# Sheet1.net
KiCad netlist of a schematic drawn in Altium Designer
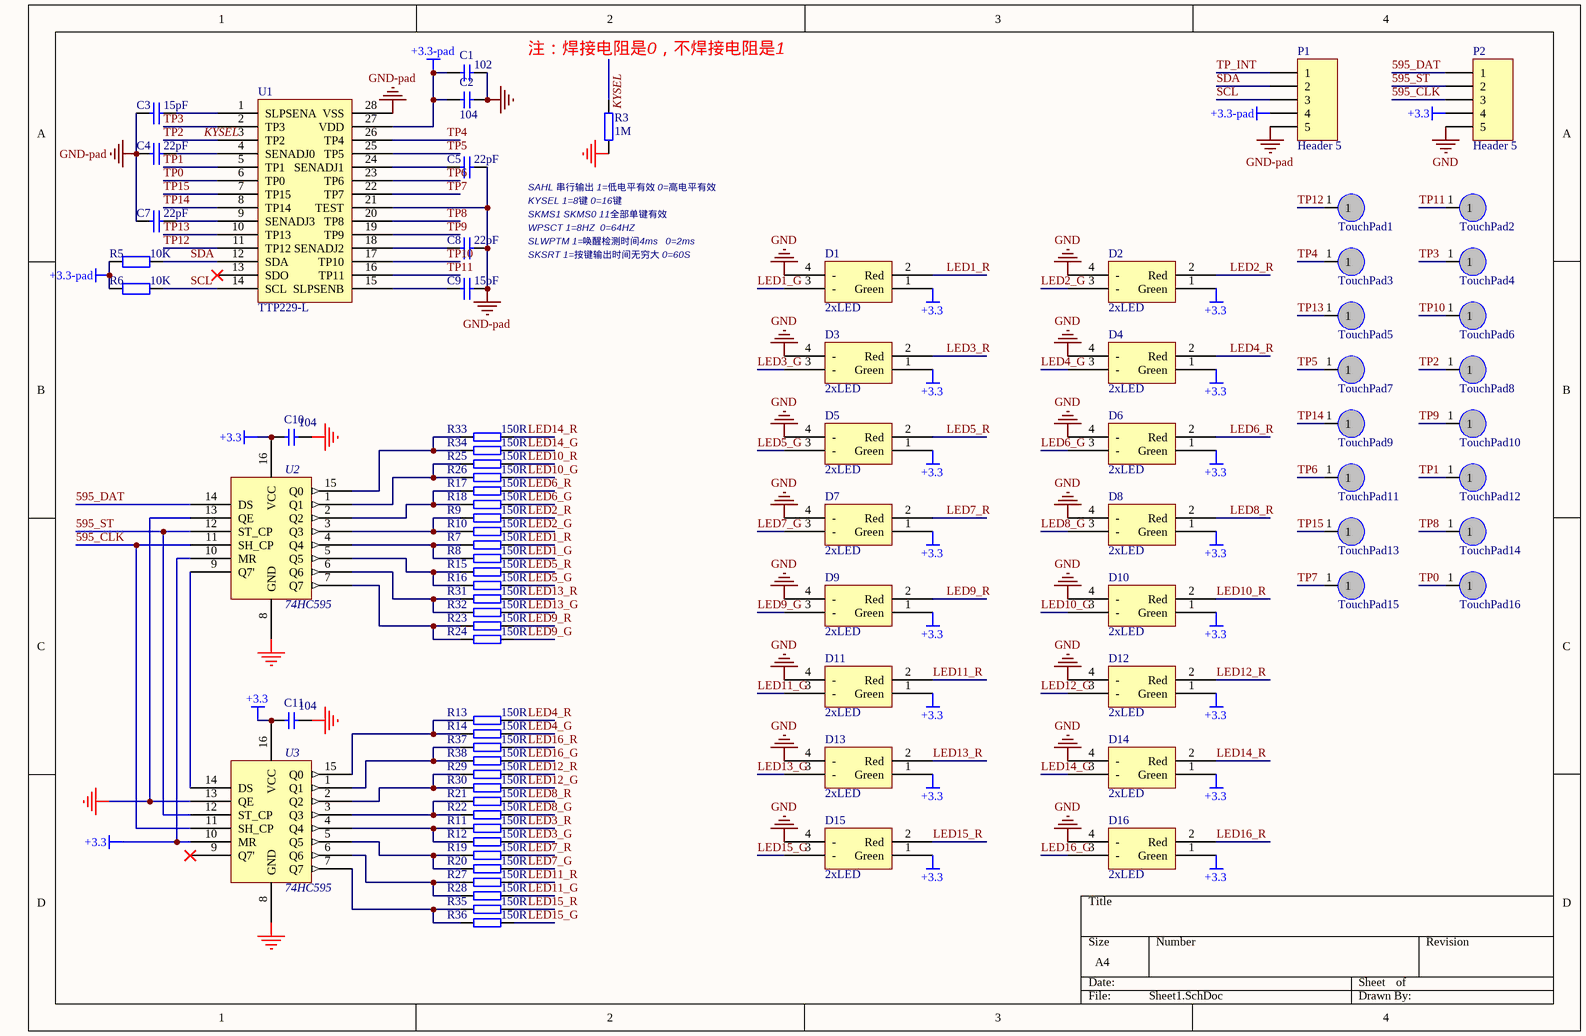
[diagram p0: Sheet1.SchDoc]

(export (version "E")
  (design (tool "Eeschema 10.0.6"))
  (components
    (comp (ref "C1")
      (value "102")
      (footprint "0603p")
      (description "0603/NPO")
      (libsource (lib "*") (part "电容-NPO-0603"))
    )
    (comp (ref "C2")
      (value "104")
      (footprint "0603p")
      (description "0603/NPO")
      (libsource (lib "*") (part "电容-NPO-0603"))
    )
    (comp (ref "C3")
      (value "15pF")
      (footprint "0603p")
      (description "Capacitor")
      (fields (field (name "PUBLISHER") "Altium Limited"))
      (libsource (lib "Miscellaneous Devices") (part "Cap"))
    )
    (comp (ref "C4")
      (value "22pF")
      (footprint "0603p")
      (description "Capacitor")
      (fields (field (name "PUBLISHER") "Altium Limited"))
      (libsource (lib "Miscellaneous Devices") (part "Cap"))
    )
    (comp (ref "C5")
      (value "22pF")
      (footprint "0603p")
      (description "Capacitor")
      (fields (field (name "PUBLISHER") "Altium Limited"))
      (libsource (lib "Miscellaneous Devices") (part "Cap"))
    )
    (comp (ref "C7")
      (value "22pF")
      (footprint "0603p")
      (description "Capacitor")
      (fields (field (name "PUBLISHER") "Altium Limited"))
      (libsource (lib "Miscellaneous Devices") (part "Cap"))
    )
    (comp (ref "C8")
      (value "22pF")
      (footprint "0603p")
      (description "Capacitor")
      (fields (field (name "PUBLISHER") "Altium Limited"))
      (libsource (lib "Miscellaneous Devices") (part "Cap"))
    )
    (comp (ref "C9")
      (value "15pF")
      (footprint "0603p")
      (description "Capacitor")
      (fields (field (name "PUBLISHER") "Altium Limited"))
      (libsource (lib "Miscellaneous Devices") (part "Cap"))
    )
    (comp (ref "C10")
      (value "104")
      (footprint "0603p")
      (description "0603/NPO")
      (libsource (lib "*") (part "电容-NPO-0603"))
    )
    (comp (ref "C11")
      (value "104")
      (footprint "0603p")
      (description "0603/NPO")
      (libsource (lib "*") (part "电容-NPO-0603"))
    )
    (comp (ref "D1") (value "2xLED") (footprint "LED") (libsource (lib "Schlib1") (part "2xLED")))
    (comp (ref "D2") (value "2xLED") (footprint "LED") (libsource (lib "Schlib1") (part "2xLED")))
    (comp (ref "D3") (value "2xLED") (footprint "LED") (libsource (lib "Schlib1") (part "2xLED")))
    (comp (ref "D4") (value "2xLED") (footprint "LED") (libsource (lib "Schlib1") (part "2xLED")))
    (comp (ref "D5") (value "2xLED") (footprint "LED") (libsource (lib "Schlib1") (part "2xLED")))
    (comp (ref "D6") (value "2xLED") (footprint "LED") (libsource (lib "Schlib1") (part "2xLED")))
    (comp (ref "D7") (value "2xLED") (footprint "LED") (libsource (lib "Schlib1") (part "2xLED")))
    (comp (ref "D8") (value "2xLED") (footprint "LED") (libsource (lib "Schlib1") (part "2xLED")))
    (comp (ref "D9") (value "2xLED") (footprint "LED") (libsource (lib "Schlib1") (part "2xLED")))
    (comp (ref "D10") (value "2xLED") (footprint "LED") (libsource (lib "Schlib1") (part "2xLED")))
    (comp (ref "D11") (value "2xLED") (footprint "LED") (libsource (lib "Schlib1") (part "2xLED")))
    (comp (ref "D12") (value "2xLED") (footprint "LED") (libsource (lib "Schlib1") (part "2xLED")))
    (comp (ref "D13") (value "2xLED") (footprint "LED") (libsource (lib "Schlib1") (part "2xLED")))
    (comp (ref "D14") (value "2xLED") (footprint "LED") (libsource (lib "Schlib1") (part "2xLED")))
    (comp (ref "D15") (value "2xLED") (footprint "LED") (libsource (lib "Schlib1") (part "2xLED")))
    (comp (ref "D16") (value "2xLED") (footprint "LED") (libsource (lib "Schlib1") (part "2xLED")))
    (comp (ref "P1")
      (value "Header 5")
      (footprint "XH-5P-2.54")
      (description "Header, 5-Pin")
      (fields (field (name "PUBLISHER") "Altium Limited"))
      (libsource (lib "Miscellaneous Connectors") (part "Header 5"))
    )
    (comp (ref "P2")
      (value "Header 5")
      (footprint "XH-5P-2.54")
      (description "Header, 5-Pin")
      (fields (field (name "PUBLISHER") "Altium Limited"))
      (libsource (lib "Miscellaneous Connectors") (part "Header 5"))
    )
    (comp (ref "R3")
      (value "1M")
      (footprint "0603p")
      (description "0603/0.1000w/75v")
      (libsource (lib "*") (part "电阻-0603"))
    )
    (comp (ref "R5")
      (value "10K")
      (footprint "0603p")
      (description "Resistor")
      (fields (field (name "PUBLISHER") "Altium Limited"))
      (libsource (lib "Miscellaneous Devices") (part "Res2"))
    )
    (comp (ref "R6")
      (value "10K")
      (footprint "0603p")
      (description "Resistor")
      (fields (field (name "PUBLISHER") "Altium Limited"))
      (libsource (lib "Miscellaneous Devices") (part "Res2"))
    )
    (comp (ref "R7")
      (value "150R")
      (footprint "0603p")
      (description "0603/0.1000w/75v")
      (libsource (lib "*") (part "电阻-0603"))
    )
    (comp (ref "R8")
      (value "150R")
      (footprint "0603p")
      (description "0603/0.1000w/75v")
      (libsource (lib "*") (part "电阻-0603"))
    )
    (comp (ref "R9")
      (value "150R")
      (footprint "0603p")
      (description "0603/0.1000w/75v")
      (libsource (lib "*") (part "电阻-0603"))
    )
    (comp (ref "R10")
      (value "150R")
      (footprint "0603p")
      (description "0603/0.1000w/75v")
      (libsource (lib "*") (part "电阻-0603"))
    )
    (comp (ref "R11")
      (value "150R")
      (footprint "0603p")
      (description "0603/0.1000w/75v")
      (libsource (lib "*") (part "电阻-0603"))
    )
    (comp (ref "R12")
      (value "150R")
      (footprint "0603p")
      (description "0603/0.1000w/75v")
      (libsource (lib "*") (part "电阻-0603"))
    )
    (comp (ref "R13")
      (value "150R")
      (footprint "0603p")
      (description "0603/0.1000w/75v")
      (libsource (lib "*") (part "电阻-0603"))
    )
    (comp (ref "R14")
      (value "150R")
      (footprint "0603p")
      (description "0603/0.1000w/75v")
      (libsource (lib "*") (part "电阻-0603"))
    )
    (comp (ref "R15")
      (value "150R")
      (footprint "0603p")
      (description "0603/0.1000w/75v")
      (libsource (lib "*") (part "电阻-0603"))
    )
    (comp (ref "R16")
      (value "150R")
      (footprint "0603p")
      (description "0603/0.1000w/75v")
      (libsource (lib "*") (part "电阻-0603"))
    )
    (comp (ref "R17")
      (value "150R")
      (footprint "0603p")
      (description "0603/0.1000w/75v")
      (libsource (lib "*") (part "电阻-0603"))
    )
    (comp (ref "R18")
      (value "150R")
      (footprint "0603p")
      (description "0603/0.1000w/75v")
      (libsource (lib "*") (part "电阻-0603"))
    )
    (comp (ref "R19")
      (value "150R")
      (footprint "0603p")
      (description "0603/0.1000w/75v")
      (libsource (lib "*") (part "电阻-0603"))
    )
    (comp (ref "R20")
      (value "150R")
      (footprint "0603p")
      (description "0603/0.1000w/75v")
      (libsource (lib "*") (part "电阻-0603"))
    )
    (comp (ref "R21")
      (value "150R")
      (footprint "0603p")
      (description "0603/0.1000w/75v")
      (libsource (lib "*") (part "电阻-0603"))
    )
    (comp (ref "R22")
      (value "150R")
      (footprint "0603p")
      (description "0603/0.1000w/75v")
      (libsource (lib "*") (part "电阻-0603"))
    )
    (comp (ref "R23")
      (value "150R")
      (footprint "0603p")
      (description "0603/0.1000w/75v")
      (libsource (lib "*") (part "电阻-0603"))
    )
    (comp (ref "R24")
      (value "150R")
      (footprint "0603p")
      (description "0603/0.1000w/75v")
      (libsource (lib "*") (part "电阻-0603"))
    )
    (comp (ref "R25")
      (value "150R")
      (footprint "0603p")
      (description "0603/0.1000w/75v")
      (libsource (lib "*") (part "电阻-0603"))
    )
    (comp (ref "R26")
      (value "150R")
      (footprint "0603p")
      (description "0603/0.1000w/75v")
      (libsource (lib "*") (part "电阻-0603"))
    )
    (comp (ref "R27")
      (value "150R")
      (footprint "0603p")
      (description "0603/0.1000w/75v")
      (libsource (lib "*") (part "电阻-0603"))
    )
    (comp (ref "R28")
      (value "150R")
      (footprint "0603p")
      (description "0603/0.1000w/75v")
      (libsource (lib "*") (part "电阻-0603"))
    )
    (comp (ref "R29")
      (value "150R")
      (footprint "0603p")
      (description "0603/0.1000w/75v")
      (libsource (lib "*") (part "电阻-0603"))
    )
    (comp (ref "R30")
      (value "150R")
      (footprint "0603p")
      (description "0603/0.1000w/75v")
      (libsource (lib "*") (part "电阻-0603"))
    )
    (comp (ref "R31")
      (value "150R")
      (footprint "0603p")
      (description "0603/0.1000w/75v")
      (libsource (lib "*") (part "电阻-0603"))
    )
    (comp (ref "R32")
      (value "150R")
      (footprint "0603p")
      (description "0603/0.1000w/75v")
      (libsource (lib "*") (part "电阻-0603"))
    )
    (comp (ref "R33")
      (value "150R")
      (footprint "0603p")
      (description "0603/0.1000w/75v")
      (libsource (lib "*") (part "电阻-0603"))
    )
    (comp (ref "R34")
      (value "150R")
      (footprint "0603p")
      (description "0603/0.1000w/75v")
      (libsource (lib "*") (part "电阻-0603"))
    )
    (comp (ref "R35")
      (value "150R")
      (footprint "0603p")
      (description "0603/0.1000w/75v")
      (libsource (lib "*") (part "电阻-0603"))
    )
    (comp (ref "R36")
      (value "150R")
      (footprint "0603p")
      (description "0603/0.1000w/75v")
      (libsource (lib "*") (part "电阻-0603"))
    )
    (comp (ref "R37")
      (value "150R")
      (footprint "0603p")
      (description "0603/0.1000w/75v")
      (libsource (lib "*") (part "电阻-0603"))
    )
    (comp (ref "R38")
      (value "150R")
      (footprint "0603p")
      (description "0603/0.1000w/75v")
      (libsource (lib "*") (part "电阻-0603"))
    )
    (comp (ref "TouchPad1")
      (value "TouchPad")
      (footprint "TOUCHKEYBIG")
      (libsource (lib "PCB_Project1") (part "TouchPad"))
    )
    (comp (ref "TouchPad2")
      (value "TouchPad")
      (footprint "TouchKey")
      (libsource (lib "PCB_Project1") (part "TouchPad"))
    )
    (comp (ref "TouchPad3")
      (value "TouchPad")
      (footprint "TouchKey")
      (libsource (lib "PCB_Project1") (part "TouchPad"))
    )
    (comp (ref "TouchPad4")
      (value "TouchPad")
      (footprint "TOUCHKEY")
      (libsource (lib "PCB_Project1") (part "TouchPad"))
    )
    (comp (ref "TouchPad5")
      (value "TouchPad")
      (footprint "TOUCHKEYBIG")
      (libsource (lib "PCB_Project1") (part "TouchPad"))
    )
    (comp (ref "TouchPad6")
      (value "TouchPad")
      (footprint "TouchKey")
      (libsource (lib "PCB_Project1") (part "TouchPad"))
    )
    (comp (ref "TouchPad7")
      (value "TouchPad")
      (footprint "TouchKey")
      (libsource (lib "PCB_Project1") (part "TouchPad"))
    )
    (comp (ref "TouchPad8")
      (value "TouchPad")
      (footprint "TOUCHKEY")
      (libsource (lib "PCB_Project1") (part "TouchPad"))
    )
    (comp (ref "TouchPad9")
      (value "TouchPad")
      (footprint "TOUCHKEYBIG")
      (libsource (lib "PCB_Project1") (part "TouchPad"))
    )
    (comp (ref "TouchPad10")
      (value "TouchPad")
      (footprint "TouchKey")
      (libsource (lib "PCB_Project1") (part "TouchPad"))
    )
    (comp (ref "TouchPad11")
      (value "TouchPad")
      (footprint "TouchKey")
      (libsource (lib "PCB_Project1") (part "TouchPad"))
    )
    (comp (ref "TouchPad12")
      (value "TouchPad")
      (footprint "TOUCHKEY")
      (libsource (lib "PCB_Project1") (part "TouchPad"))
    )
    (comp (ref "TouchPad13")
      (value "TouchPad")
      (footprint "TOUCHKEYBIG")
      (libsource (lib "PCB_Project1") (part "TouchPad"))
    )
    (comp (ref "TouchPad14")
      (value "TouchPad")
      (footprint "TouchKey")
      (libsource (lib "PCB_Project1") (part "TouchPad"))
    )
    (comp (ref "TouchPad15")
      (value "TouchPad")
      (footprint "TOUCHKEY")
      (libsource (lib "PCB_Project1") (part "TouchPad"))
    )
    (comp (ref "TouchPad16")
      (value "TouchPad")
      (footprint "TOUCHKEY")
      (libsource (lib "PCB_Project1") (part "TouchPad"))
    )
    (comp (ref "U1")
      (value "TTP229-L")
      (footprint "LC-SSOP-28_150mil")
      (libsource (lib "Schlib1") (part "TTP229-L"))
    )
    (comp (ref "U2") (value "74HC595") (footprint "LC-SOP-16_150mil") (libsource (lib "*") (part "74HCT595")))
    (comp (ref "U3") (value "74HC595") (footprint "LC-SOP-16_150mil") (libsource (lib "*") (part "74HCT595")))
  )
  (nets
    (net (code "1") (name "+3.3") (class "Default")
      (node (ref "C10") (pin "1") (pinfunction "1_1") (pintype "passive"))
      (node (ref "C11") (pin "1") (pinfunction "1_1") (pintype "passive"))
      (node (ref "D1") (pin "1") (pinfunction "Green_1") (pintype "passive"))
      (node (ref "D10") (pin "1") (pinfunction "Green_1") (pintype "passive"))
      (node (ref "D11") (pin "1") (pinfunction "Green_1") (pintype "passive"))
      (node (ref "D12") (pin "1") (pinfunction "Green_1") (pintype "passive"))
      (node (ref "D13") (pin "1") (pinfunction "Green_1") (pintype "passive"))
      (node (ref "D14") (pin "1") (pinfunction "Green_1") (pintype "passive"))
      (node (ref "D15") (pin "1") (pinfunction "Green_1") (pintype "passive"))
      (node (ref "D16") (pin "1") (pinfunction "Green_1") (pintype "passive"))
      (node (ref "D2") (pin "1") (pinfunction "Green_1") (pintype "passive"))
      (node (ref "D3") (pin "1") (pinfunction "Green_1") (pintype "passive"))
      (node (ref "D4") (pin "1") (pinfunction "Green_1") (pintype "passive"))
      (node (ref "D5") (pin "1") (pinfunction "Green_1") (pintype "passive"))
      (node (ref "D6") (pin "1") (pinfunction "Green_1") (pintype "passive"))
      (node (ref "D7") (pin "1") (pinfunction "Green_1") (pintype "passive"))
      (node (ref "D8") (pin "1") (pinfunction "Green_1") (pintype "passive"))
      (node (ref "D9") (pin "1") (pinfunction "Green_1") (pintype "passive"))
      (node (ref "P2") (pin "4") (pinfunction "4_4") (pintype "passive"))
      (node (ref "U2") (pin "10") (pinfunction "MR_10") (pintype "passive"))
      (node (ref "U2") (pin "16") (pinfunction "VCC_16") (pintype "power_in"))
      (node (ref "U3") (pin "10") (pinfunction "MR_10") (pintype "passive"))
      (node (ref "U3") (pin "16") (pinfunction "VCC_16") (pintype "power_in"))
    )
    (net (code "2") (name "+3.3-pad") (class "Default")
      (node (ref "C1") (pin "1") (pinfunction "1_1") (pintype "passive"))
      (node (ref "C2") (pin "1") (pinfunction "1_1") (pintype "passive"))
      (node (ref "P1") (pin "4") (pinfunction "4_4") (pintype "passive"))
      (node (ref "R5") (pin "1") (pinfunction "1_1") (pintype "passive"))
      (node (ref "R6") (pin "1") (pinfunction "1_1") (pintype "passive"))
      (node (ref "U1") (pin "27") (pinfunction "VDD_27") (pintype "passive"))
    )
    (net (code "3") (name "/595_CLK") (class "Default")
      (node (ref "P2") (pin "3") (pinfunction "3_3") (pintype "passive"))
      (node (ref "U2") (pin "11") (pinfunction "SH_CP_11") (pintype "passive"))
      (node (ref "U3") (pin "11") (pinfunction "SH_CP_11") (pintype "passive"))
    )
    (net (code "4") (name "/595_DAT") (class "Default")
      (node (ref "P2") (pin "1") (pinfunction "1_1") (pintype "passive"))
      (node (ref "U2") (pin "14") (pinfunction "DS_14") (pintype "passive"))
    )
    (net (code "5") (name "/595_ST") (class "Default")
      (node (ref "P2") (pin "2") (pinfunction "2_2") (pintype "passive"))
      (node (ref "U2") (pin "12") (pinfunction "ST_CP_12") (pintype "passive"))
      (node (ref "U3") (pin "12") (pinfunction "ST_CP_12") (pintype "passive"))
    )
    (net (code "6") (name "/KYSEL") (class "Default")
      (node (ref "R3") (pin "1") (pinfunction "1_1") (pintype "passive"))
      (node (ref "TouchPad8") (pin "1") (pinfunction "1_1") (pintype "passive"))
      (node (ref "U1") (pin "3") (pinfunction "TP2_3") (pintype "passive"))
    )
    (net (code "7") (name "/LED1_G") (class "Default")
      (node (ref "D1") (pin "3") (pinfunction "-_3") (pintype "passive"))
      (node (ref "R8") (pin "2") (pinfunction "2_2") (pintype "passive"))
    )
    (net (code "8") (name "/LED1_R") (class "Default")
      (node (ref "D1") (pin "2") (pinfunction "Red_2") (pintype "passive"))
      (node (ref "R7") (pin "2") (pinfunction "2_2") (pintype "passive"))
    )
    (net (code "9") (name "/LED2_G") (class "Default")
      (node (ref "D2") (pin "3") (pinfunction "-_3") (pintype "passive"))
      (node (ref "R10") (pin "2") (pinfunction "2_2") (pintype "passive"))
    )
    (net (code "10") (name "/LED2_R") (class "Default")
      (node (ref "D2") (pin "2") (pinfunction "Red_2") (pintype "passive"))
      (node (ref "R9") (pin "2") (pinfunction "2_2") (pintype "passive"))
    )
    (net (code "11") (name "/LED3_G") (class "Default")
      (node (ref "D3") (pin "3") (pinfunction "-_3") (pintype "passive"))
      (node (ref "R12") (pin "2") (pinfunction "2_2") (pintype "passive"))
    )
    (net (code "12") (name "/LED3_R") (class "Default")
      (node (ref "D3") (pin "2") (pinfunction "Red_2") (pintype "passive"))
      (node (ref "R11") (pin "2") (pinfunction "2_2") (pintype "passive"))
    )
    (net (code "13") (name "/LED4_G") (class "Default")
      (node (ref "D4") (pin "3") (pinfunction "-_3") (pintype "passive"))
      (node (ref "R14") (pin "2") (pinfunction "2_2") (pintype "passive"))
    )
    (net (code "14") (name "/LED4_R") (class "Default")
      (node (ref "D4") (pin "2") (pinfunction "Red_2") (pintype "passive"))
      (node (ref "R13") (pin "2") (pinfunction "2_2") (pintype "passive"))
    )
    (net (code "15") (name "/LED5_G") (class "Default")
      (node (ref "D5") (pin "3") (pinfunction "-_3") (pintype "passive"))
      (node (ref "R16") (pin "2") (pinfunction "2_2") (pintype "passive"))
    )
    (net (code "16") (name "/LED5_R") (class "Default")
      (node (ref "D5") (pin "2") (pinfunction "Red_2") (pintype "passive"))
      (node (ref "R15") (pin "2") (pinfunction "2_2") (pintype "passive"))
    )
    (net (code "17") (name "/LED6_G") (class "Default")
      (node (ref "D6") (pin "3") (pinfunction "-_3") (pintype "passive"))
      (node (ref "R18") (pin "2") (pinfunction "2_2") (pintype "passive"))
    )
    (net (code "18") (name "/LED6_R") (class "Default")
      (node (ref "D6") (pin "2") (pinfunction "Red_2") (pintype "passive"))
      (node (ref "R17") (pin "2") (pinfunction "2_2") (pintype "passive"))
    )
    (net (code "19") (name "/LED7_G") (class "Default")
      (node (ref "D7") (pin "3") (pinfunction "-_3") (pintype "passive"))
      (node (ref "R20") (pin "2") (pinfunction "2_2") (pintype "passive"))
    )
    (net (code "20") (name "/LED7_R") (class "Default")
      (node (ref "D7") (pin "2") (pinfunction "Red_2") (pintype "passive"))
      (node (ref "R19") (pin "2") (pinfunction "2_2") (pintype "passive"))
    )
    (net (code "21") (name "/LED8_G") (class "Default")
      (node (ref "D8") (pin "3") (pinfunction "-_3") (pintype "passive"))
      (node (ref "R22") (pin "2") (pinfunction "2_2") (pintype "passive"))
    )
    (net (code "22") (name "/LED8_R") (class "Default")
      (node (ref "D8") (pin "2") (pinfunction "Red_2") (pintype "passive"))
      (node (ref "R21") (pin "2") (pinfunction "2_2") (pintype "passive"))
    )
    (net (code "23") (name "/LED9_G") (class "Default")
      (node (ref "D9") (pin "3") (pinfunction "-_3") (pintype "passive"))
      (node (ref "R24") (pin "2") (pinfunction "2_2") (pintype "passive"))
    )
    (net (code "24") (name "/LED9_R") (class "Default")
      (node (ref "D9") (pin "2") (pinfunction "Red_2") (pintype "passive"))
      (node (ref "R23") (pin "2") (pinfunction "2_2") (pintype "passive"))
    )
    (net (code "25") (name "/LED10_G") (class "Default")
      (node (ref "D10") (pin "3") (pinfunction "-_3") (pintype "passive"))
      (node (ref "R26") (pin "2") (pinfunction "2_2") (pintype "passive"))
    )
    (net (code "26") (name "/LED10_R") (class "Default")
      (node (ref "D10") (pin "2") (pinfunction "Red_2") (pintype "passive"))
      (node (ref "R25") (pin "2") (pinfunction "2_2") (pintype "passive"))
    )
    (net (code "27") (name "/LED11_G") (class "Default")
      (node (ref "D11") (pin "3") (pinfunction "-_3") (pintype "passive"))
      (node (ref "R28") (pin "2") (pinfunction "2_2") (pintype "passive"))
    )
    (net (code "28") (name "/LED11_R") (class "Default")
      (node (ref "D11") (pin "2") (pinfunction "Red_2") (pintype "passive"))
      (node (ref "R27") (pin "2") (pinfunction "2_2") (pintype "passive"))
    )
    (net (code "29") (name "/LED12_G") (class "Default")
      (node (ref "D12") (pin "3") (pinfunction "-_3") (pintype "passive"))
      (node (ref "R30") (pin "2") (pinfunction "2_2") (pintype "passive"))
    )
    (net (code "30") (name "/LED12_R") (class "Default")
      (node (ref "D12") (pin "2") (pinfunction "Red_2") (pintype "passive"))
      (node (ref "R29") (pin "2") (pinfunction "2_2") (pintype "passive"))
    )
    (net (code "31") (name "/LED13_G") (class "Default")
      (node (ref "D13") (pin "3") (pinfunction "-_3") (pintype "passive"))
      (node (ref "R32") (pin "2") (pinfunction "2_2") (pintype "passive"))
    )
    (net (code "32") (name "/LED13_R") (class "Default")
      (node (ref "D13") (pin "2") (pinfunction "Red_2") (pintype "passive"))
      (node (ref "R31") (pin "2") (pinfunction "2_2") (pintype "passive"))
    )
    (net (code "33") (name "/LED14_G") (class "Default")
      (node (ref "D14") (pin "3") (pinfunction "-_3") (pintype "passive"))
      (node (ref "R34") (pin "2") (pinfunction "2_2") (pintype "passive"))
    )
    (net (code "34") (name "/LED14_R") (class "Default")
      (node (ref "D14") (pin "2") (pinfunction "Red_2") (pintype "passive"))
      (node (ref "R33") (pin "2") (pinfunction "2_2") (pintype "passive"))
    )
    (net (code "35") (name "/LED15_G") (class "Default")
      (node (ref "D15") (pin "3") (pinfunction "-_3") (pintype "passive"))
      (node (ref "R36") (pin "2") (pinfunction "2_2") (pintype "passive"))
    )
    (net (code "36") (name "/LED15_R") (class "Default")
      (node (ref "D15") (pin "2") (pinfunction "Red_2") (pintype "passive"))
      (node (ref "R35") (pin "2") (pinfunction "2_2") (pintype "passive"))
    )
    (net (code "37") (name "/LED16_G") (class "Default")
      (node (ref "D16") (pin "3") (pinfunction "-_3") (pintype "passive"))
      (node (ref "R38") (pin "2") (pinfunction "2_2") (pintype "passive"))
    )
    (net (code "38") (name "/LED16_R") (class "Default")
      (node (ref "D16") (pin "2") (pinfunction "Red_2") (pintype "passive"))
      (node (ref "R37") (pin "2") (pinfunction "2_2") (pintype "passive"))
    )
    (net (code "39") (name "/SCL") (class "Default")
      (node (ref "P1") (pin "3") (pinfunction "3_3") (pintype "passive"))
      (node (ref "R6") (pin "2") (pinfunction "2_2") (pintype "passive"))
      (node (ref "U1") (pin "14") (pinfunction "SCL_14") (pintype "passive"))
    )
    (net (code "40") (name "/SDA") (class "Default")
      (node (ref "P1") (pin "2") (pinfunction "2_2") (pintype "passive"))
      (node (ref "R5") (pin "2") (pinfunction "2_2") (pintype "passive"))
      (node (ref "U1") (pin "12") (pinfunction "SDA_12") (pintype "passive"))
    )
    (net (code "41") (name "/TP0") (class "Default")
      (node (ref "TouchPad16") (pin "1") (pinfunction "1_1") (pintype "passive"))
      (node (ref "U1") (pin "6") (pinfunction "TP0_6") (pintype "passive"))
    )
    (net (code "42") (name "/TP1") (class "Default")
      (node (ref "TouchPad12") (pin "1") (pinfunction "1_1") (pintype "passive"))
      (node (ref "U1") (pin "5") (pinfunction "TP1_5") (pintype "passive"))
    )
    (net (code "43") (name "/TP3") (class "Default")
      (node (ref "TouchPad4") (pin "1") (pinfunction "1_1") (pintype "passive"))
      (node (ref "U1") (pin "2") (pinfunction "TP3_2") (pintype "passive"))
    )
    (net (code "44") (name "/TP4") (class "Default")
      (node (ref "TouchPad3") (pin "1") (pinfunction "1_1") (pintype "passive"))
      (node (ref "U1") (pin "26") (pinfunction "TP4_26") (pintype "passive"))
    )
    (net (code "45") (name "/TP5") (class "Default")
      (node (ref "TouchPad7") (pin "1") (pinfunction "1_1") (pintype "passive"))
      (node (ref "U1") (pin "25") (pinfunction "TP5_25") (pintype "passive"))
    )
    (net (code "46") (name "/TP6") (class "Default")
      (node (ref "TouchPad11") (pin "1") (pinfunction "1_1") (pintype "passive"))
      (node (ref "U1") (pin "23") (pinfunction "TP6_23") (pintype "passive"))
    )
    (net (code "47") (name "/TP7") (class "Default")
      (node (ref "TouchPad15") (pin "1") (pinfunction "1_1") (pintype "passive"))
      (node (ref "U1") (pin "22") (pinfunction "TP7_22") (pintype "passive"))
    )
    (net (code "48") (name "/TP8") (class "Default")
      (node (ref "TouchPad14") (pin "1") (pinfunction "1_1") (pintype "passive"))
      (node (ref "U1") (pin "20") (pinfunction "TP8_20") (pintype "passive"))
    )
    (net (code "49") (name "/TP9") (class "Default")
      (node (ref "TouchPad10") (pin "1") (pinfunction "1_1") (pintype "passive"))
      (node (ref "U1") (pin "19") (pinfunction "TP9_19") (pintype "passive"))
    )
    (net (code "50") (name "/TP10") (class "Default")
      (node (ref "TouchPad6") (pin "1") (pinfunction "1_1") (pintype "passive"))
      (node (ref "U1") (pin "17") (pinfunction "TP10_17") (pintype "passive"))
    )
    (net (code "51") (name "/TP11") (class "Default")
      (node (ref "TouchPad2") (pin "1") (pinfunction "1_1") (pintype "passive"))
      (node (ref "U1") (pin "16") (pinfunction "TP11_16") (pintype "passive"))
    )
    (net (code "52") (name "/TP12") (class "Default")
      (node (ref "TouchPad1") (pin "1") (pinfunction "1_1") (pintype "passive"))
      (node (ref "U1") (pin "11") (pinfunction "TP12_11") (pintype "passive"))
    )
    (net (code "53") (name "/TP13") (class "Default")
      (node (ref "TouchPad5") (pin "1") (pinfunction "1_1") (pintype "passive"))
      (node (ref "U1") (pin "10") (pinfunction "TP13_10") (pintype "passive"))
    )
    (net (code "54") (name "/TP14") (class "Default")
      (node (ref "TouchPad9") (pin "1") (pinfunction "1_1") (pintype "passive"))
      (node (ref "U1") (pin "8") (pinfunction "TP14_8") (pintype "passive"))
    )
    (net (code "55") (name "/TP15") (class "Default")
      (node (ref "TouchPad13") (pin "1") (pinfunction "1_1") (pintype "passive"))
      (node (ref "U1") (pin "7") (pinfunction "TP15_7") (pintype "passive"))
    )
    (net (code "56") (name "/TP_INT") (class "Default")
      (node (ref "P1") (pin "1") (pinfunction "1_1") (pintype "passive"))
    )
    (net (code "57") (name "GND") (class "Default")
      (node (ref "C10") (pin "2") (pinfunction "2_2") (pintype "passive"))
      (node (ref "C11") (pin "2") (pinfunction "2_2") (pintype "passive"))
      (node (ref "D1") (pin "4") (pinfunction "-_4") (pintype "passive"))
      (node (ref "D10") (pin "4") (pinfunction "-_4") (pintype "passive"))
      (node (ref "D11") (pin "4") (pinfunction "-_4") (pintype "passive"))
      (node (ref "D12") (pin "4") (pinfunction "-_4") (pintype "passive"))
      (node (ref "D13") (pin "4") (pinfunction "-_4") (pintype "passive"))
      (node (ref "D14") (pin "4") (pinfunction "-_4") (pintype "passive"))
      (node (ref "D15") (pin "4") (pinfunction "-_4") (pintype "passive"))
      (node (ref "D16") (pin "4") (pinfunction "-_4") (pintype "passive"))
      (node (ref "D2") (pin "4") (pinfunction "-_4") (pintype "passive"))
      (node (ref "D3") (pin "4") (pinfunction "-_4") (pintype "passive"))
      (node (ref "D4") (pin "4") (pinfunction "-_4") (pintype "passive"))
      (node (ref "D5") (pin "4") (pinfunction "-_4") (pintype "passive"))
      (node (ref "D6") (pin "4") (pinfunction "-_4") (pintype "passive"))
      (node (ref "D7") (pin "4") (pinfunction "-_4") (pintype "passive"))
      (node (ref "D8") (pin "4") (pinfunction "-_4") (pintype "passive"))
      (node (ref "D9") (pin "4") (pinfunction "-_4") (pintype "passive"))
      (node (ref "P2") (pin "5") (pinfunction "5_5") (pintype "passive"))
      (node (ref "U2") (pin "13") (pinfunction "QE_13") (pintype "passive"))
      (node (ref "U2") (pin "8") (pinfunction "GND_8") (pintype "power_in"))
      (node (ref "U3") (pin "13") (pinfunction "QE_13") (pintype "passive"))
      (node (ref "U3") (pin "8") (pinfunction "GND_8") (pintype "power_in"))
    )
    (net (code "58") (name "GND-pad") (class "Default")
      (node (ref "C1") (pin "2") (pinfunction "2_2") (pintype "passive"))
      (node (ref "C2") (pin "2") (pinfunction "2_2") (pintype "passive"))
      (node (ref "C3") (pin "1") (pinfunction "1_1") (pintype "passive"))
      (node (ref "C4") (pin "1") (pinfunction "1_1") (pintype "passive"))
      (node (ref "C5") (pin "2") (pinfunction "2_2") (pintype "passive"))
      (node (ref "C7") (pin "1") (pinfunction "1_1") (pintype "passive"))
      (node (ref "C8") (pin "2") (pinfunction "2_2") (pintype "passive"))
      (node (ref "C9") (pin "2") (pinfunction "2_2") (pintype "passive"))
      (node (ref "P1") (pin "5") (pinfunction "5_5") (pintype "passive"))
      (node (ref "R3") (pin "2") (pinfunction "2_2") (pintype "passive"))
      (node (ref "U1") (pin "21") (pinfunction "TEST_21") (pintype "passive"))
      (node (ref "U1") (pin "28") (pinfunction "VSS_28") (pintype "passive"))
    )
    (net (code "59") (name "Net-(U1-SENADJ0)") (class "Default")
      (node (ref "C4") (pin "2") (pinfunction "2_2") (pintype "passive"))
      (node (ref "U1") (pin "4") (pinfunction "SENADJ0_4") (pintype "passive"))
    )
    (net (code "60") (name "Net-(U1-SENADJ1)") (class "Default")
      (node (ref "C5") (pin "1") (pinfunction "1_1") (pintype "passive"))
      (node (ref "U1") (pin "24") (pinfunction "SENADJ1_24") (pintype "passive"))
    )
    (net (code "61") (name "Net-(U1-SENADJ2)") (class "Default")
      (node (ref "C8") (pin "1") (pinfunction "1_1") (pintype "passive"))
      (node (ref "U1") (pin "18") (pinfunction "SENADJ2_18") (pintype "passive"))
    )
    (net (code "62") (name "Net-(U1-SENADJ3)") (class "Default")
      (node (ref "C7") (pin "2") (pinfunction "2_2") (pintype "passive"))
      (node (ref "U1") (pin "9") (pinfunction "SENADJ3_9") (pintype "passive"))
    )
    (net (code "63") (name "Net-(U1-SLPSENA)") (class "Default")
      (node (ref "C3") (pin "2") (pinfunction "2_2") (pintype "passive"))
      (node (ref "U1") (pin "1") (pinfunction "SLPSENA_1") (pintype "passive"))
    )
    (net (code "64") (name "Net-(U1-SLPSENB)") (class "Default")
      (node (ref "C9") (pin "1") (pinfunction "1_1") (pintype "passive"))
      (node (ref "U1") (pin "15") (pinfunction "SLPSENB_15") (pintype "passive"))
    )
    (net (code "65") (name "Net-(U2-Q0)") (class "Default")
      (node (ref "R33") (pin "1") (pinfunction "1_1") (pintype "passive"))
      (node (ref "R34") (pin "1") (pinfunction "1_1") (pintype "passive"))
      (node (ref "U2") (pin "15") (pinfunction "Q0_15") (pintype "output"))
    )
    (net (code "66") (name "Net-(U2-Q1)") (class "Default")
      (node (ref "R25") (pin "1") (pinfunction "1_1") (pintype "passive"))
      (node (ref "R26") (pin "1") (pinfunction "1_1") (pintype "passive"))
      (node (ref "U2") (pin "1") (pinfunction "Q1_1") (pintype "output"))
    )
    (net (code "67") (name "Net-(U2-Q2)") (class "Default")
      (node (ref "R17") (pin "1") (pinfunction "1_1") (pintype "passive"))
      (node (ref "R18") (pin "1") (pinfunction "1_1") (pintype "passive"))
      (node (ref "U2") (pin "2") (pinfunction "Q2_2") (pintype "output"))
    )
    (net (code "68") (name "Net-(U2-Q3)") (class "Default")
      (node (ref "R10") (pin "1") (pinfunction "1_1") (pintype "passive"))
      (node (ref "R9") (pin "1") (pinfunction "1_1") (pintype "passive"))
      (node (ref "U2") (pin "3") (pinfunction "Q3_3") (pintype "output"))
    )
    (net (code "69") (name "Net-(U2-Q4)") (class "Default")
      (node (ref "R7") (pin "1") (pinfunction "1_1") (pintype "passive"))
      (node (ref "R8") (pin "1") (pinfunction "1_1") (pintype "passive"))
      (node (ref "U2") (pin "4") (pinfunction "Q4_4") (pintype "output"))
    )
    (net (code "70") (name "Net-(U2-Q5)") (class "Default")
      (node (ref "R15") (pin "1") (pinfunction "1_1") (pintype "passive"))
      (node (ref "R16") (pin "1") (pinfunction "1_1") (pintype "passive"))
      (node (ref "U2") (pin "5") (pinfunction "Q5_5") (pintype "output"))
    )
    (net (code "71") (name "Net-(U2-Q6)") (class "Default")
      (node (ref "R31") (pin "1") (pinfunction "1_1") (pintype "passive"))
      (node (ref "R32") (pin "1") (pinfunction "1_1") (pintype "passive"))
      (node (ref "U2") (pin "6") (pinfunction "Q6_6") (pintype "output"))
    )
    (net (code "72") (name "Net-(U2-Q7')") (class "Default")
      (node (ref "U2") (pin "9") (pinfunction "Q7'_9") (pintype "passive"))
      (node (ref "U3") (pin "14") (pinfunction "DS_14") (pintype "passive"))
    )
    (net (code "73") (name "Net-(U2-Q7)") (class "Default")
      (node (ref "R23") (pin "1") (pinfunction "1_1") (pintype "passive"))
      (node (ref "R24") (pin "1") (pinfunction "1_1") (pintype "passive"))
      (node (ref "U2") (pin "7") (pinfunction "Q7_7") (pintype "output"))
    )
    (net (code "74") (name "Net-(U3-Q0)") (class "Default")
      (node (ref "R13") (pin "1") (pinfunction "1_1") (pintype "passive"))
      (node (ref "R14") (pin "1") (pinfunction "1_1") (pintype "passive"))
      (node (ref "U3") (pin "15") (pinfunction "Q0_15") (pintype "output"))
    )
    (net (code "75") (name "Net-(U3-Q1)") (class "Default")
      (node (ref "R37") (pin "1") (pinfunction "1_1") (pintype "passive"))
      (node (ref "R38") (pin "1") (pinfunction "1_1") (pintype "passive"))
      (node (ref "U3") (pin "1") (pinfunction "Q1_1") (pintype "output"))
    )
    (net (code "76") (name "Net-(U3-Q2)") (class "Default")
      (node (ref "R29") (pin "1") (pinfunction "1_1") (pintype "passive"))
      (node (ref "R30") (pin "1") (pinfunction "1_1") (pintype "passive"))
      (node (ref "U3") (pin "2") (pinfunction "Q2_2") (pintype "output"))
    )
    (net (code "77") (name "Net-(U3-Q3)") (class "Default")
      (node (ref "R21") (pin "1") (pinfunction "1_1") (pintype "passive"))
      (node (ref "R22") (pin "1") (pinfunction "1_1") (pintype "passive"))
      (node (ref "U3") (pin "3") (pinfunction "Q3_3") (pintype "output"))
    )
    (net (code "78") (name "Net-(U3-Q4)") (class "Default")
      (node (ref "R11") (pin "1") (pinfunction "1_1") (pintype "passive"))
      (node (ref "R12") (pin "1") (pinfunction "1_1") (pintype "passive"))
      (node (ref "U3") (pin "4") (pinfunction "Q4_4") (pintype "output"))
    )
    (net (code "79") (name "Net-(U3-Q5)") (class "Default")
      (node (ref "R19") (pin "1") (pinfunction "1_1") (pintype "passive"))
      (node (ref "R20") (pin "1") (pinfunction "1_1") (pintype "passive"))
      (node (ref "U3") (pin "5") (pinfunction "Q5_5") (pintype "output"))
    )
    (net (code "80") (name "Net-(U3-Q6)") (class "Default")
      (node (ref "R27") (pin "1") (pinfunction "1_1") (pintype "passive"))
      (node (ref "R28") (pin "1") (pinfunction "1_1") (pintype "passive"))
      (node (ref "U3") (pin "6") (pinfunction "Q6_6") (pintype "output"))
    )
    (net (code "81") (name "Net-(U3-Q7)") (class "Default")
      (node (ref "R35") (pin "1") (pinfunction "1_1") (pintype "passive"))
      (node (ref "R36") (pin "1") (pinfunction "1_1") (pintype "passive"))
      (node (ref "U3") (pin "7") (pinfunction "Q7_7") (pintype "output"))
    )
    (net (code "82") (name "unconnected-(U1-SDO-Pad13)") (class "Default")
      (node (ref "U1") (pin "13") (pinfunction "SDO_13") (pintype "passive+no_connect"))
    )
    (net (code "83") (name "unconnected-(U3-Q7'-Pad9)") (class "Default")
      (node (ref "U3") (pin "9") (pinfunction "Q7'_9") (pintype "passive+no_connect"))
    )
  )
)
